# Battery.net
KiCad netlist of a schematic drawn in Altium Designer
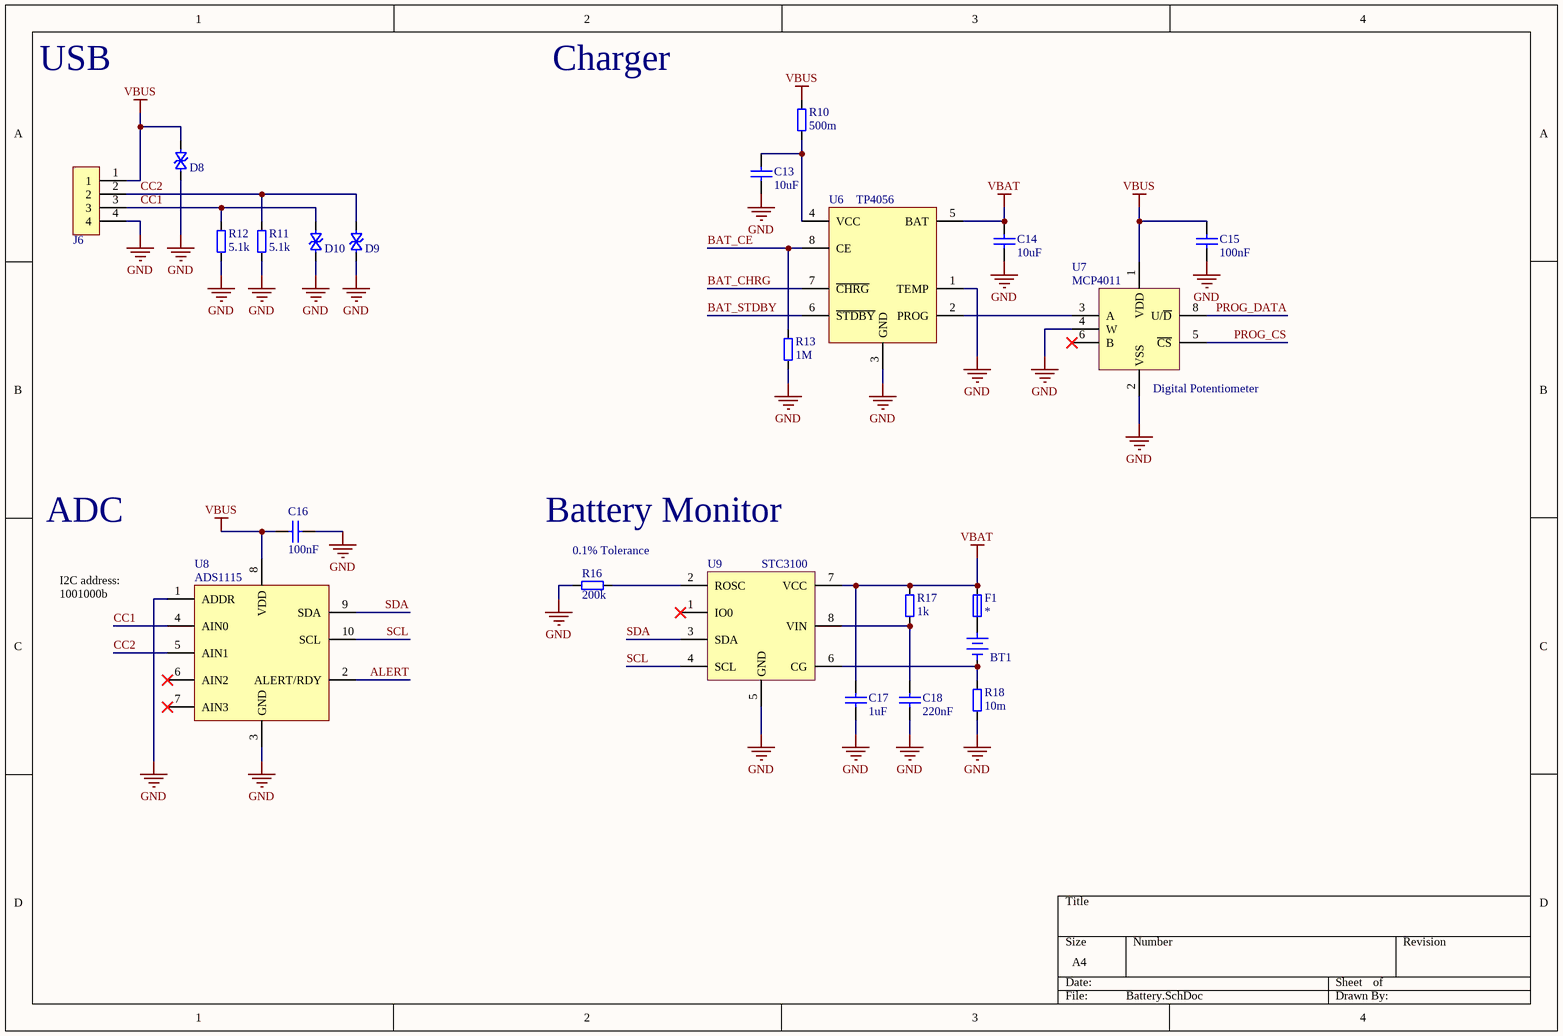
[diagram p0: Battery.SchDoc]

(export (version "E")
  (design (tool "Eeschema 10.0.6"))
  (components
    (comp (ref "BT1")
      (value "18650")
      (footprint "1x2 Header")
      (libsource (lib "CustomModule") (part "18650"))
    )
    (comp (ref "C13")
      (value "Capacitor_10uF")
      (footprint "CAP 0805")
      (fields (field (name "CAPACITANCE") "10uF"))
      (libsource (lib "BasicComponents") (part "Capacitor_10uF"))
    )
    (comp (ref "C14")
      (value "Capacitor_10uF")
      (footprint "CAP 0805")
      (fields (field (name "CAPACITANCE") "10uF"))
      (libsource (lib "BasicComponents") (part "Capacitor_10uF"))
    )
    (comp (ref "C15")
      (value "Capacitor_100nF")
      (footprint "CAP 0805")
      (fields (field (name "CAPACITANCE") "100nF"))
      (libsource (lib "BasicComponents") (part "Capacitor_100nF"))
    )
    (comp (ref "C16")
      (value "Capacitor_100nF")
      (footprint "CAP 0805")
      (fields (field (name "CAPACITANCE") "100nF"))
      (libsource (lib "BasicComponents") (part "Capacitor_100nF"))
    )
    (comp (ref "C17")
      (value "Capacitor_1uF")
      (footprint "CAP 0805")
      (fields (field (name "CAPACITANCE") "1uF"))
      (libsource (lib "BasicComponents") (part "Capacitor_1uF"))
    )
    (comp (ref "C18")
      (value "Capacitor_220nF")
      (footprint "CAP 0805")
      (fields (field (name "CAPACITANCE") "220nF"))
      (libsource (lib "BasicComponents") (part "Capacitor_220nF"))
    )
    (comp (ref "D8")
      (value "Diode_TVS_Bi")
      (footprint "DIOM4226X24N")
      (libsource (lib "BasicComponents") (part "Diode_TVS_Bi"))
    )
    (comp (ref "D9")
      (value "Diode_TVS_Bi")
      (footprint "DIOM4226X24N")
      (libsource (lib "BasicComponents") (part "Diode_TVS_Bi"))
    )
    (comp (ref "D10")
      (value "Diode_TVS_Bi")
      (footprint "DIOM4226X24N")
      (libsource (lib "BasicComponents") (part "Diode_TVS_Bi"))
    )
    (comp (ref "F1")
      (value "Fuse")
      (footprint "RES 0805")
      (fields (field (name "TRIP CURRENT") "*"))
      (libsource (lib "BasicComponents") (part "Fuse"))
    )
    (comp (ref "J6")
      (value "1x4 Header")
      (footprint "1x4 Header")
      (libsource (lib "BasicConnectors") (part "1x4_Header"))
    )
    (comp (ref "R10")
      (value "Resistor_500m")
      (footprint "Axial Resistor THT")
      (fields (field (name "RESISTANCE") "500m"))
      (libsource (lib "BasicComponents") (part "Resistor_500m"))
    )
    (comp (ref "R11")
      (value "Resistor_5.1k")
      (footprint "RES 0805")
      (fields (field (name "RESISTANCE") "5.1k"))
      (libsource (lib "BasicComponents") (part "Resistor_5.1k"))
    )
    (comp (ref "R12")
      (value "Resistor_5.1k")
      (footprint "RES 0805")
      (fields (field (name "RESISTANCE") "5.1k"))
      (libsource (lib "BasicComponents") (part "Resistor_5.1k"))
    )
    (comp (ref "R13")
      (value "Resistor_1M")
      (footprint "RES 0805")
      (fields (field (name "RESISTANCE") "1M"))
      (libsource (lib "BasicComponents") (part "Resistor_1M"))
    )
    (comp (ref "R16")
      (value "Resistor_200k")
      (footprint "RES 0805")
      (fields (field (name "RESISTANCE") "200k"))
      (libsource (lib "BasicComponents") (part "Resistor_200k"))
    )
    (comp (ref "R17")
      (value "Resistor_1k")
      (footprint "RES 0805")
      (fields (field (name "RESISTANCE") "1k"))
      (libsource (lib "BasicComponents") (part "Resistor_1k"))
    )
    (comp (ref "R18")
      (value "Resistor_10m")
      (footprint "RES 0805")
      (fields (field (name "RESISTANCE") "10m"))
      (libsource (lib "BasicComponents") (part "Resistor_10m"))
    )
    (comp (ref "U6")
      (value "TP4056")
      (footprint "SOP-8N w/ Thermal Pad")
      (libsource (lib "CustomModule") (part "TP4056"))
    )
    (comp (ref "U7")
      (value "MCP4011")
      (footprint "TSOP65P490X110-8N")
      (description "Digital POT")
      (libsource (lib "CustomModule") (part "MCP4011"))
    )
    (comp (ref "U8")
      (value "ADS1115")
      (footprint "TSSOP50P490X110-10N")
      (description "16-bit, ADC, I2C")
      (libsource (lib "CustomModule") (part "ADS1115"))
    )
    (comp (ref "U9")
      (value "STC3100")
      (footprint "TSOP65P490X110-8N")
      (libsource (lib "CustomModule") (part "STC3100"))
    )
  )
  (nets
    (net (code "1") (name "/ALERT") (class "Default")
      (node (ref "U8") (pin "2") (pinfunction "ALERT/RDY_2") (pintype "passive"))
    )
    (net (code "2") (name "/BAT_CE") (class "Default")
      (node (ref "R13") (pin "2") (pintype "passive"))
      (node (ref "U6") (pin "8") (pinfunction "CE_8") (pintype "passive"))
    )
    (net (code "3") (name "/BAT_CHRG") (class "Default")
      (node (ref "U6") (pin "7") (pinfunction "~{CHRG}_7") (pintype "passive"))
    )
    (net (code "4") (name "/BAT_STDBY") (class "Default")
      (node (ref "U6") (pin "6") (pinfunction "~{STDBY}_6") (pintype "passive"))
    )
    (net (code "5") (name "/CC1") (class "Default")
      (node (ref "D10") (pin "1") (pintype "passive"))
      (node (ref "J6") (pin "3") (pinfunction "3_3") (pintype "passive"))
      (node (ref "R12") (pin "2") (pintype "passive"))
      (node (ref "U8") (pin "4") (pinfunction "AIN0_4") (pintype "passive"))
    )
    (net (code "6") (name "/CC2") (class "Default")
      (node (ref "D9") (pin "1") (pintype "passive"))
      (node (ref "J6") (pin "2") (pinfunction "2_2") (pintype "passive"))
      (node (ref "R11") (pin "2") (pintype "passive"))
      (node (ref "U8") (pin "5") (pinfunction "AIN1_5") (pintype "passive"))
    )
    (net (code "7") (name "/PROG_CS") (class "Default")
      (node (ref "U7") (pin "5") (pinfunction "~{CS}_5") (pintype "passive"))
    )
    (net (code "8") (name "/PROG_DATA") (class "Default")
      (node (ref "U7") (pin "8") (pinfunction "U/~{D}_8") (pintype "passive"))
    )
    (net (code "9") (name "/SCL") (class "Default")
      (node (ref "U8") (pin "10") (pinfunction "SCL_10") (pintype "passive"))
      (node (ref "U9") (pin "4") (pinfunction "SCL_4") (pintype "passive"))
    )
    (net (code "10") (name "/SDA") (class "Default")
      (node (ref "U8") (pin "9") (pinfunction "SDA_9") (pintype "passive"))
      (node (ref "U9") (pin "3") (pinfunction "SDA_3") (pintype "passive"))
    )
    (net (code "11") (name "GND") (class "Default")
      (node (ref "C13") (pin "1") (pintype "passive"))
      (node (ref "C14") (pin "1") (pintype "passive"))
      (node (ref "C15") (pin "1") (pintype "passive"))
      (node (ref "C16") (pin "1") (pintype "passive"))
      (node (ref "C17") (pin "2") (pintype "passive"))
      (node (ref "C18") (pin "1") (pintype "passive"))
      (node (ref "D10") (pin "2") (pintype "passive"))
      (node (ref "D8") (pin "2") (pintype "passive"))
      (node (ref "D9") (pin "2") (pintype "passive"))
      (node (ref "J6") (pin "4") (pinfunction "4_4") (pintype "passive"))
      (node (ref "R11") (pin "1") (pintype "passive"))
      (node (ref "R12") (pin "1") (pintype "passive"))
      (node (ref "R13") (pin "1") (pintype "passive"))
      (node (ref "R16") (pin "1") (pintype "passive"))
      (node (ref "R18") (pin "1") (pintype "passive"))
      (node (ref "U6") (pin "1") (pinfunction "TEMP_1") (pintype "passive"))
      (node (ref "U6") (pin "3") (pinfunction "GND_3") (pintype "passive"))
      (node (ref "U7") (pin "2") (pinfunction "VSS_2") (pintype "passive"))
      (node (ref "U7") (pin "4") (pinfunction "W_4") (pintype "passive"))
      (node (ref "U8") (pin "1") (pinfunction "ADDR_1") (pintype "passive"))
      (node (ref "U8") (pin "3") (pinfunction "GND_3") (pintype "passive"))
      (node (ref "U9") (pin "5") (pinfunction "GND_5") (pintype "passive"))
    )
    (net (code "12") (name "Net-(BT1-Pad1)") (class "Default")
      (node (ref "BT1") (pin "1") (pintype "passive"))
      (node (ref "F1") (pin "1") (pintype "passive"))
    )
    (net (code "13") (name "Net-(U6-PROG)") (class "Default")
      (node (ref "U6") (pin "2") (pinfunction "PROG_2") (pintype "passive"))
      (node (ref "U7") (pin "3") (pinfunction "A_3") (pintype "passive"))
    )
    (net (code "14") (name "Net-(U6-VCC)") (class "Default")
      (node (ref "C13") (pin "2") (pintype "passive"))
      (node (ref "R10") (pin "1") (pintype "passive"))
      (node (ref "U6") (pin "4") (pinfunction "VCC_4") (pintype "passive"))
    )
    (net (code "15") (name "Net-(U9-CG)") (class "Default")
      (node (ref "BT1") (pin "2") (pintype "passive"))
      (node (ref "R18") (pin "2") (pintype "passive"))
      (node (ref "U9") (pin "6") (pinfunction "CG_6") (pintype "passive"))
    )
    (net (code "16") (name "Net-(U9-ROSC)") (class "Default")
      (node (ref "R16") (pin "2") (pintype "passive"))
      (node (ref "U9") (pin "2") (pinfunction "ROSC_2") (pintype "passive"))
    )
    (net (code "17") (name "Net-(U9-VIN)") (class "Default")
      (node (ref "C18") (pin "2") (pintype "passive"))
      (node (ref "R17") (pin "1") (pintype "passive"))
      (node (ref "U9") (pin "8") (pinfunction "VIN_8") (pintype "passive"))
    )
    (net (code "18") (name "VBAT") (class "Default")
      (node (ref "C14") (pin "2") (pintype "passive"))
      (node (ref "C17") (pin "1") (pintype "passive"))
      (node (ref "F1") (pin "2") (pintype "passive"))
      (node (ref "R17") (pin "2") (pintype "passive"))
      (node (ref "U6") (pin "5") (pinfunction "BAT_5") (pintype "passive"))
      (node (ref "U9") (pin "7") (pinfunction "VCC_7") (pintype "passive"))
    )
    (net (code "19") (name "VBUS") (class "Default")
      (node (ref "C15") (pin "2") (pintype "passive"))
      (node (ref "C16") (pin "2") (pintype "passive"))
      (node (ref "D8") (pin "1") (pintype "passive"))
      (node (ref "J6") (pin "1") (pinfunction "1_1") (pintype "passive"))
      (node (ref "R10") (pin "2") (pintype "passive"))
      (node (ref "U7") (pin "1") (pinfunction "VDD_1") (pintype "passive"))
      (node (ref "U8") (pin "8") (pinfunction "VDD_8") (pintype "passive"))
    )
    (net (code "20") (name "unconnected-(U7-B-Pad6)") (class "Default")
      (node (ref "U7") (pin "6") (pinfunction "B_6") (pintype "passive+no_connect"))
    )
    (net (code "21") (name "unconnected-(U8-AIN2-Pad6)") (class "Default")
      (node (ref "U8") (pin "6") (pinfunction "AIN2_6") (pintype "passive+no_connect"))
    )
    (net (code "22") (name "unconnected-(U8-AIN3-Pad7)") (class "Default")
      (node (ref "U8") (pin "7") (pinfunction "AIN3_7") (pintype "passive+no_connect"))
    )
    (net (code "23") (name "unconnected-(U9-IO0-Pad1)") (class "Default")
      (node (ref "U9") (pin "1") (pinfunction "IO0_1") (pintype "passive+no_connect"))
    )
  )
)
